# JacdacTBlockButton_62.net
KiCad netlist of a schematic drawn in Altium Designer
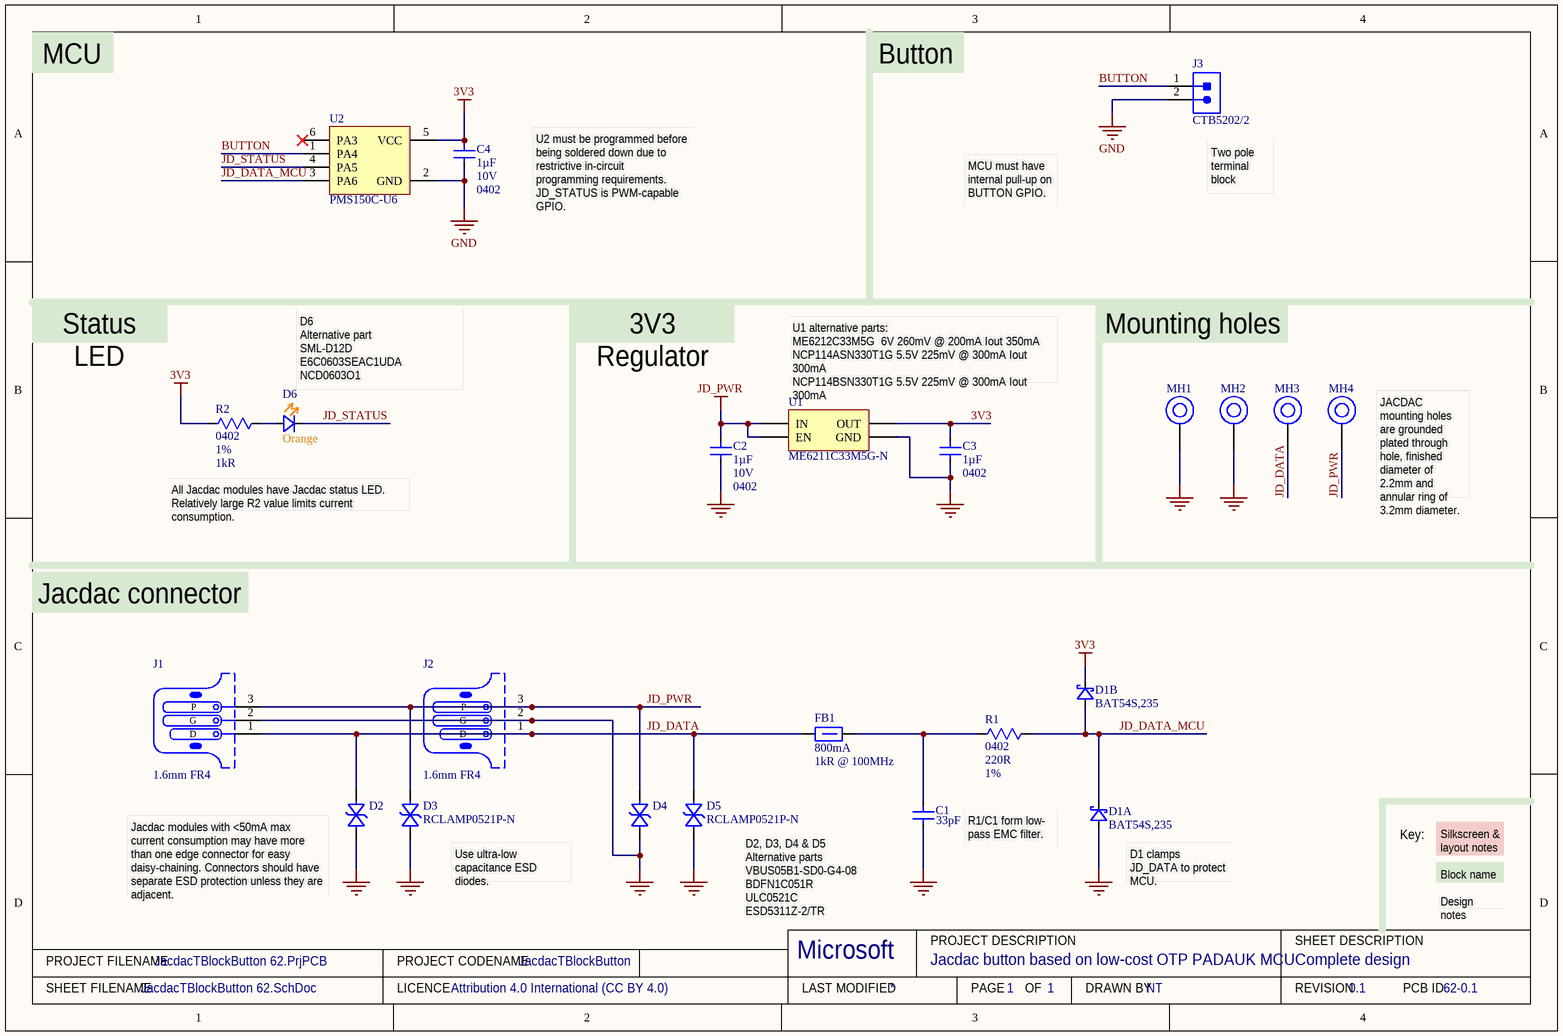
[diagram p0: JacdacTBlockButton 62.SchDoc]

(export (version "E")
  (design (tool "Eeschema 10.0.6"))
  (components
    (comp (ref "C1")
      (value "CL05C330JB5NNNC")
      (footprint "C0402_0.55MM - without outline")
      (description "CAP CER 33PF 50V C0G/NP0 0402")
      (fields
        (field (name "MANUFACTURER") "Samsung")
        (field (name "TOLERANCE") "5%")
        (field (name "CAPACITANCE") "33pF")
      )
      (libsource (lib "Samsung") (part "CL05C330JB5NNNC"))
    )
    (comp (ref "C2")
      (value "CL05A105KP5NNNC")
      (footprint "C0402_0.55MM - without outline")
      (description "CAP CER 1UF 10V X5R 0402")
      (fields
        (field (name "MANUFACTURER") "Samsung")
        (field (name "TOLERANCE") "10%")
        (field (name "CAPACITANCE") "1µF")
        (field (name "VOLTAGE RATING") "10V")
        (field (name "CASE CODE (IMPERIAL)") "0402")
        (field (name "CREATED") "DG")
        (field (name "CHECKED") "?")
      )
      (libsource (lib "Samsung") (part "CL05A105KP5NNNC"))
    )
    (comp (ref "C3")
      (value "CL05A105KP5NNNC")
      (footprint "C0402_0.55MM - without outline")
      (description "CAP CER 1UF 10V X5R 0402")
      (fields
        (field (name "MANUFACTURER") "Samsung")
        (field (name "TOLERANCE") "10%")
        (field (name "CAPACITANCE") "1µF")
        (field (name "CASE CODE (IMPERIAL)") "0402")
        (field (name "CREATED") "DG")
        (field (name "CHECKED") "?")
      )
      (libsource (lib "Samsung") (part "CL05A105KP5NNNC"))
    )
    (comp (ref "C4")
      (value "CL05A105KP5NNNC")
      (footprint "C0402_0.55MM - without outline")
      (description "CAP CER 1UF 10V X5R 0402")
      (fields
        (field (name "MANUFACTURER") "Samsung")
        (field (name "TOLERANCE") "10%")
        (field (name "CAPACITANCE") "1µF")
        (field (name "VOLTAGE RATING") "10V")
        (field (name "CASE CODE (IMPERIAL)") "0402")
        (field (name "CREATED") "DG")
        (field (name "CHECKED") "?")
      )
      (libsource (lib "Samsung") (part "CL05A105KP5NNNC"))
    )
    (comp (ref "D1")
      (value "BAT54S")
      (footprint "NXP-BAT54S-TO-236AB - without outline")
      (description "DIODE ARRAY SCHOTTKY 30V SOT23")
      (fields (field (name "MANUFACTURER") "Nexperia") (field (name "MANUFACTURER PART NUMBER") "BAT54S,235"))
      (libsource (lib "NXP") (part "BAT54S"))
    )
    (comp (ref "D2")
      (value "RCLAMP0521P-N")
      (footprint "TVS 0402 - L")
      (description "Bidirectional 5V (Max) 6V 16V 3.5A (8/20us) 0402 TVS RoHS")
      (fields
        (field (name "MANUFACTURER") "Born Semiconductor")
        (field (name "CREATED BY") "D Gakure")
        (field (name "CHECKED BY") "?")
      )
      (libsource (lib "BornSemiconductor") (part "RCLAMP0521P-N"))
    )
    (comp (ref "D3")
      (value "RCLAMP0521P-N")
      (footprint "TVS 0402 - L")
      (description "Bidirectional 5V (Max) 6V 16V 3.5A (8/20us) 0402 TVS RoHS")
      (fields
        (field (name "MANUFACTURER") "Born Semiconductor")
        (field (name "MANUFACTURER PART NUMBER") "RCLAMP0521P-N")
        (field (name "CREATED BY") "D Gakure")
        (field (name "CHECKED BY") "?")
      )
      (libsource (lib "BornSemiconductor") (part "RCLAMP0521P-N"))
    )
    (comp (ref "D4")
      (value "RCLAMP0521P-N")
      (footprint "TVS 0402 - L")
      (description "Bidirectional 5V (Max) 6V 16V 3.5A (8/20us) 0402 TVS RoHS")
      (fields
        (field (name "MANUFACTURER") "Born Semiconductor")
        (field (name "CREATED BY") "D Gakure")
        (field (name "CHECKED BY") "?")
      )
      (libsource (lib "BornSemiconductor") (part "RCLAMP0521P-N"))
    )
    (comp (ref "D5")
      (value "RCLAMP0521P-N")
      (footprint "TVS 0402 - L")
      (description "Bidirectional 5V (Max) 6V 16V 3.5A (8/20us) 0402 TVS RoHS")
      (fields
        (field (name "MANUFACTURER") "Born Semiconductor")
        (field (name "MANUFACTURER PART NUMBER") "RCLAMP0521P-N")
        (field (name "CREATED BY") "D Gakure")
        (field (name "CHECKED BY") "?")
      )
      (libsource (lib "BornSemiconductor") (part "RCLAMP0521P-N"))
    )
    (comp (ref "D6")
      (value "~")
      (footprint "0603 Orange - without outline")
      (description "LED ORANGE DIFFUSED 1608 SMD")
      (fields
        (field (name "MANUFACTURER") "Everlight Elec")
        (field (name "MANUFACTURER PART NUMBER") "19-217/S2C-AQ1R1B/3T")
        (field (name "COLOUR") "Orange")
      )
      (libsource (lib "EverlightElec") (part "19-217/S2C-AQ1R1B/3T"))
    )
    (comp (ref "FB1")
      (value "TDK MPZ1608S102ATA00")
      (footprint "TDK MPZ1608 0.8mm - without outline")
      (description "0603 1k@100MHz 0.8A chip")
      (fields
        (field (name "TOLERANCE") "25%")
        (field (name "MANUFACTURER") "TDK")
        (field (name "CURRENT RATING") "800mA")
        (field (name "IMPEDANCE") "1kR @ 100MHz")
      )
      (libsource (lib "TDK") (part "TDK MPZ1608S102ATA00"))
    )
    (comp (ref "J1")
      (value "3 pin JACDAC edge connector")
      (footprint "JACDAC_EDGE_CONNECTOR_NO_TRACES")
      (description "3 pin Jacdac edge connector 1.27mm pitch")
      (fields
        (field (name "MANUFACTURER PART NUMBER") "JACDAC_EDGE_CONNECTOR")
        (field (name "PCB TYPE") "1.6mm FR4")
        (field (name "CHECKED BY") "?")
        (field (name "CREATED BY") "D. Gakure")
      )
      (libsource (lib "generic-con") (part "Jacdac edge connector"))
    )
    (comp (ref "J2")
      (value "3 pin JACDAC edge connector")
      (footprint "JACDAC_EDGE_CONNECTOR_NO_TRACES")
      (description "3 pin Jacdac edge connector 1.27mm pitch")
      (fields
        (field (name "MANUFACTURER PART NUMBER") "JACDAC_EDGE_CONNECTOR")
        (field (name "PCB TYPE") "1.6mm FR4")
        (field (name "CHECKED BY") "?")
        (field (name "CREATED BY") "D. Gakure")
      )
      (libsource (lib "generic-con") (part "Jacdac edge connector"))
    )
    (comp (ref "J3")
      (value "TERMINAL BLOCK, WIRE TO BRD, 2POS")
      (footprint "CAMDENBOSS_CTB5202-2:CTB5202-2")
      (description "CAMDENBOSS - CTB5202/2 - TERMINAL BLOCK, WIRE TO BRD, 2POS")
      (fields
        (field (name "MANUFACTURER") "Camden Electronics Boss")
        (field (name "MANUFACTURER PART NUMBER") "CTB5202/2")
      )
      (libsource (lib "CamdenBoss") (part "CTB5202/2"))
    )
    (comp (ref "MH1")
      (value "MH_5.0MMK_3.0MMC_2.1MMD_PTH")
      (footprint "MH_5.0MMK_3.0MMC_2.1MMD_PTH")
      (description "Mounting Hole 5.0mm keepout, 3.0mm annualar ring and 2.1mm Drill PTH")
      (libsource (lib "generic") (part "MH_5.0MMK_3.0MMC_2.1MMD_PTH"))
    )
    (comp (ref "MH2")
      (value "MH_5.0MMK_3.0MMC_2.1MMD_PTH")
      (footprint "MH_5.0MMK_3.0MMC_2.1MMD_PTH")
      (description "Mounting Hole 5.0mm keepout, 3.0mm annualar ring and 2.1mm Drill PTH")
      (libsource (lib "generic") (part "MH_5.0MMK_3.0MMC_2.1MMD_PTH"))
    )
    (comp (ref "MH3")
      (value "MH_5.0MMK_3.0MMC_2.1MMD_PTH")
      (footprint "MH_5.0MMK_3.0MMC_2.1MMD_PTH")
      (description "Mounting Hole 5.0mm keepout, 3.0mm annualar ring and 2.1mm Drill PTH")
      (libsource (lib "generic") (part "MH_5.0MMK_3.0MMC_2.1MMD_PTH"))
    )
    (comp (ref "MH4")
      (value "MH_5.0MMK_3.0MMC_2.1MMD_PTH")
      (footprint "MH_5.0MMK_3.0MMC_2.1MMD_PTH")
      (description "Mounting Hole 5.0mm keepout, 3.0mm annualar ring and 2.1mm Drill PTH")
      (libsource (lib "generic") (part "MH_5.0MMK_3.0MMC_2.1MMD_PTH"))
    )
    (comp (ref "R1")
      (value "RC0402FR-07220RL")
      (footprint "R0402 - Without outline")
      (description "RES SMD 220 OHM 1% 1/16W 0402")
      (fields
        (field (name "MANUFACTURER") "Yageo")
        (field (name "CASE CODE (IMPERIAL)") "0402")
        (field (name "RESISTANCE") "220R")
        (field (name "TOLERANCE") "1%")
        (field (name "CREATED") "D.G")
        (field (name "CHECKED") "?")
      )
      (libsource (lib "Yageo") (part "RC0402FR-07220RL"))
    )
    (comp (ref "R2")
      (value "RC0402FR-071KL")
      (footprint "R0402 - Without outline")
      (description "RES SMD 1K OHM 1% 1/16W 0402")
      (fields
        (field (name "MANUFACTURER") "Yageo")
        (field (name "CASE CODE (IMPERIAL)") "0402")
        (field (name "TOLERANCE") "1%")
        (field (name "RESISTANCE") "1kR")
        (field (name "CREATED") "D.G")
        (field (name "CHECKED") "?")
      )
      (libsource (lib "Yageo") (part "RC0402FR-071KL"))
    )
    (comp (ref "U1")
      (value "ME6211C33M5G-N")
      (footprint "MICRONE-SOT23-5")
      (description "6V 260mV @ 200mA(typ) - - Fixed 3.3V SOT-23-5 Linear Voltage Regulators (LDO) ROHS")
      (fields
        (field (name "MANUFACTURER") "MICRONE(Nanjing Micro One Elec)")
        (field (name "MANUFACTURER PART NUMBER") "ME6211C33M5G-N")
        (field (name "CREATED") "DG")
        (field (name "CHECKED") "?")
      )
      (libsource (lib "MICRONE(NanjingMicroOneElec)") (part "ME6211C33M5G-N"))
    )
    (comp (ref "U2")
      (value "PMS150C")
      (footprint "SOT23-6")
      (description "8bit OTP Type IO Controller")
      (fields (field (name "MANUFACTURER PART NUMBER") "PMS150C-U6") (field (name "MANUFACTURER") "PADAUK"))
      (libsource (lib "PADAUK") (part "PMS150C"))
    )
  )
  (nets
    (net (code "1") (name "/BUTTON") (class "Default")
      (node (ref "J3") (pin "1") (pinfunction "1_1") (pintype "passive"))
      (node (ref "U2") (pin "1") (pinfunction "PA4_1") (pintype "passive"))
    )
    (net (code "2") (name "/JD_DATA") (class "Default")
      (node (ref "D2") (pin "1") (pinfunction "K_1") (pintype "passive"))
      (node (ref "D5") (pin "1") (pinfunction "K_1") (pintype "passive"))
      (node (ref "FB1") (pin "1") (pinfunction "1_1") (pintype "passive"))
      (node (ref "J1") (pin "1") (pinfunction "D_1") (pintype "passive"))
      (node (ref "J2") (pin "1") (pinfunction "D_1") (pintype "passive"))
      (node (ref "MH3") (pin "1") (pinfunction "1_1") (pintype "passive"))
    )
    (net (code "3") (name "/JD_DATA_MCU") (class "Default")
      (node (ref "D1") (pin "3") (pinfunction "A_3") (pintype "passive"))
      (node (ref "R1") (pin "1") (pinfunction "1_1") (pintype "passive"))
      (node (ref "U2") (pin "3") (pinfunction "PA6_3") (pintype "passive"))
    )
    (net (code "4") (name "/JD_STATUS") (class "Default")
      (node (ref "D6") (pin "1") (pinfunction "K_1") (pintype "passive"))
      (node (ref "U2") (pin "4") (pinfunction "PA5_4") (pintype "passive"))
    )
    (net (code "5") (name "3V3") (class "Default")
      (node (ref "C3") (pin "2") (pinfunction "2_2") (pintype "passive"))
      (node (ref "C4") (pin "2") (pinfunction "2_2") (pintype "passive"))
      (node (ref "D1") (pin "2") (pinfunction "K_2") (pintype "passive"))
      (node (ref "R2") (pin "2") (pinfunction "2_2") (pintype "passive"))
      (node (ref "U1") (pin "5") (pinfunction "OUT_5") (pintype "passive"))
      (node (ref "U2") (pin "5") (pinfunction "VCC_5") (pintype "passive"))
    )
    (net (code "6") (name "GND") (class "Default")
      (node (ref "C1") (pin "1") (pinfunction "1_1") (pintype "passive"))
      (node (ref "C2") (pin "1") (pinfunction "1_1") (pintype "passive"))
      (node (ref "C3") (pin "1") (pinfunction "1_1") (pintype "passive"))
      (node (ref "C4") (pin "1") (pinfunction "1_1") (pintype "passive"))
      (node (ref "D1") (pin "1") (pinfunction "A_1") (pintype "passive"))
      (node (ref "D2") (pin "2") (pinfunction "A_2") (pintype "passive"))
      (node (ref "D3") (pin "2") (pinfunction "A_2") (pintype "passive"))
      (node (ref "D4") (pin "2") (pinfunction "A_2") (pintype "passive"))
      (node (ref "D5") (pin "2") (pinfunction "A_2") (pintype "passive"))
      (node (ref "J1") (pin "2") (pinfunction "G_2") (pintype "passive"))
      (node (ref "J2") (pin "2") (pinfunction "G_2") (pintype "passive"))
      (node (ref "J3") (pin "2") (pinfunction "2_2") (pintype "passive"))
      (node (ref "MH1") (pin "1") (pinfunction "1_1") (pintype "passive"))
      (node (ref "MH2") (pin "1") (pinfunction "1_1") (pintype "passive"))
      (node (ref "U1") (pin "2") (pinfunction "GND_2") (pintype "passive"))
      (node (ref "U2") (pin "2") (pinfunction "GND_2") (pintype "passive"))
    )
    (net (code "7") (name "JD_PWR") (class "Default")
      (node (ref "C2") (pin "2") (pinfunction "2_2") (pintype "passive"))
      (node (ref "D3") (pin "1") (pinfunction "K_1") (pintype "passive"))
      (node (ref "D4") (pin "1") (pinfunction "K_1") (pintype "passive"))
      (node (ref "J1") (pin "3") (pinfunction "P_3") (pintype "passive"))
      (node (ref "J2") (pin "3") (pinfunction "P_3") (pintype "passive"))
      (node (ref "MH4") (pin "1") (pinfunction "1_1") (pintype "passive"))
      (node (ref "U1") (pin "1") (pinfunction "IN_1") (pintype "passive"))
      (node (ref "U1") (pin "3") (pinfunction "EN_3") (pintype "passive"))
    )
    (net (code "8") (name "Net-(C1-Pad2)") (class "Default")
      (node (ref "C1") (pin "2") (pinfunction "2_2") (pintype "passive"))
      (node (ref "FB1") (pin "2") (pinfunction "2_2") (pintype "passive"))
      (node (ref "R1") (pin "2") (pinfunction "2_2") (pintype "passive"))
    )
    (net (code "9") (name "Net-(D6-A)") (class "Default")
      (node (ref "D6") (pin "2") (pinfunction "A_2") (pintype "passive"))
      (node (ref "R2") (pin "1") (pinfunction "1_1") (pintype "passive"))
    )
    (net (code "10") (name "unconnected-(U2-PA3-Pad6)") (class "Default")
      (node (ref "U2") (pin "6") (pinfunction "PA3_6") (pintype "passive+no_connect"))
    )
  )
)
